# template_attiny_44.net
KiCad netlist of a schematic drawn in EAGLE
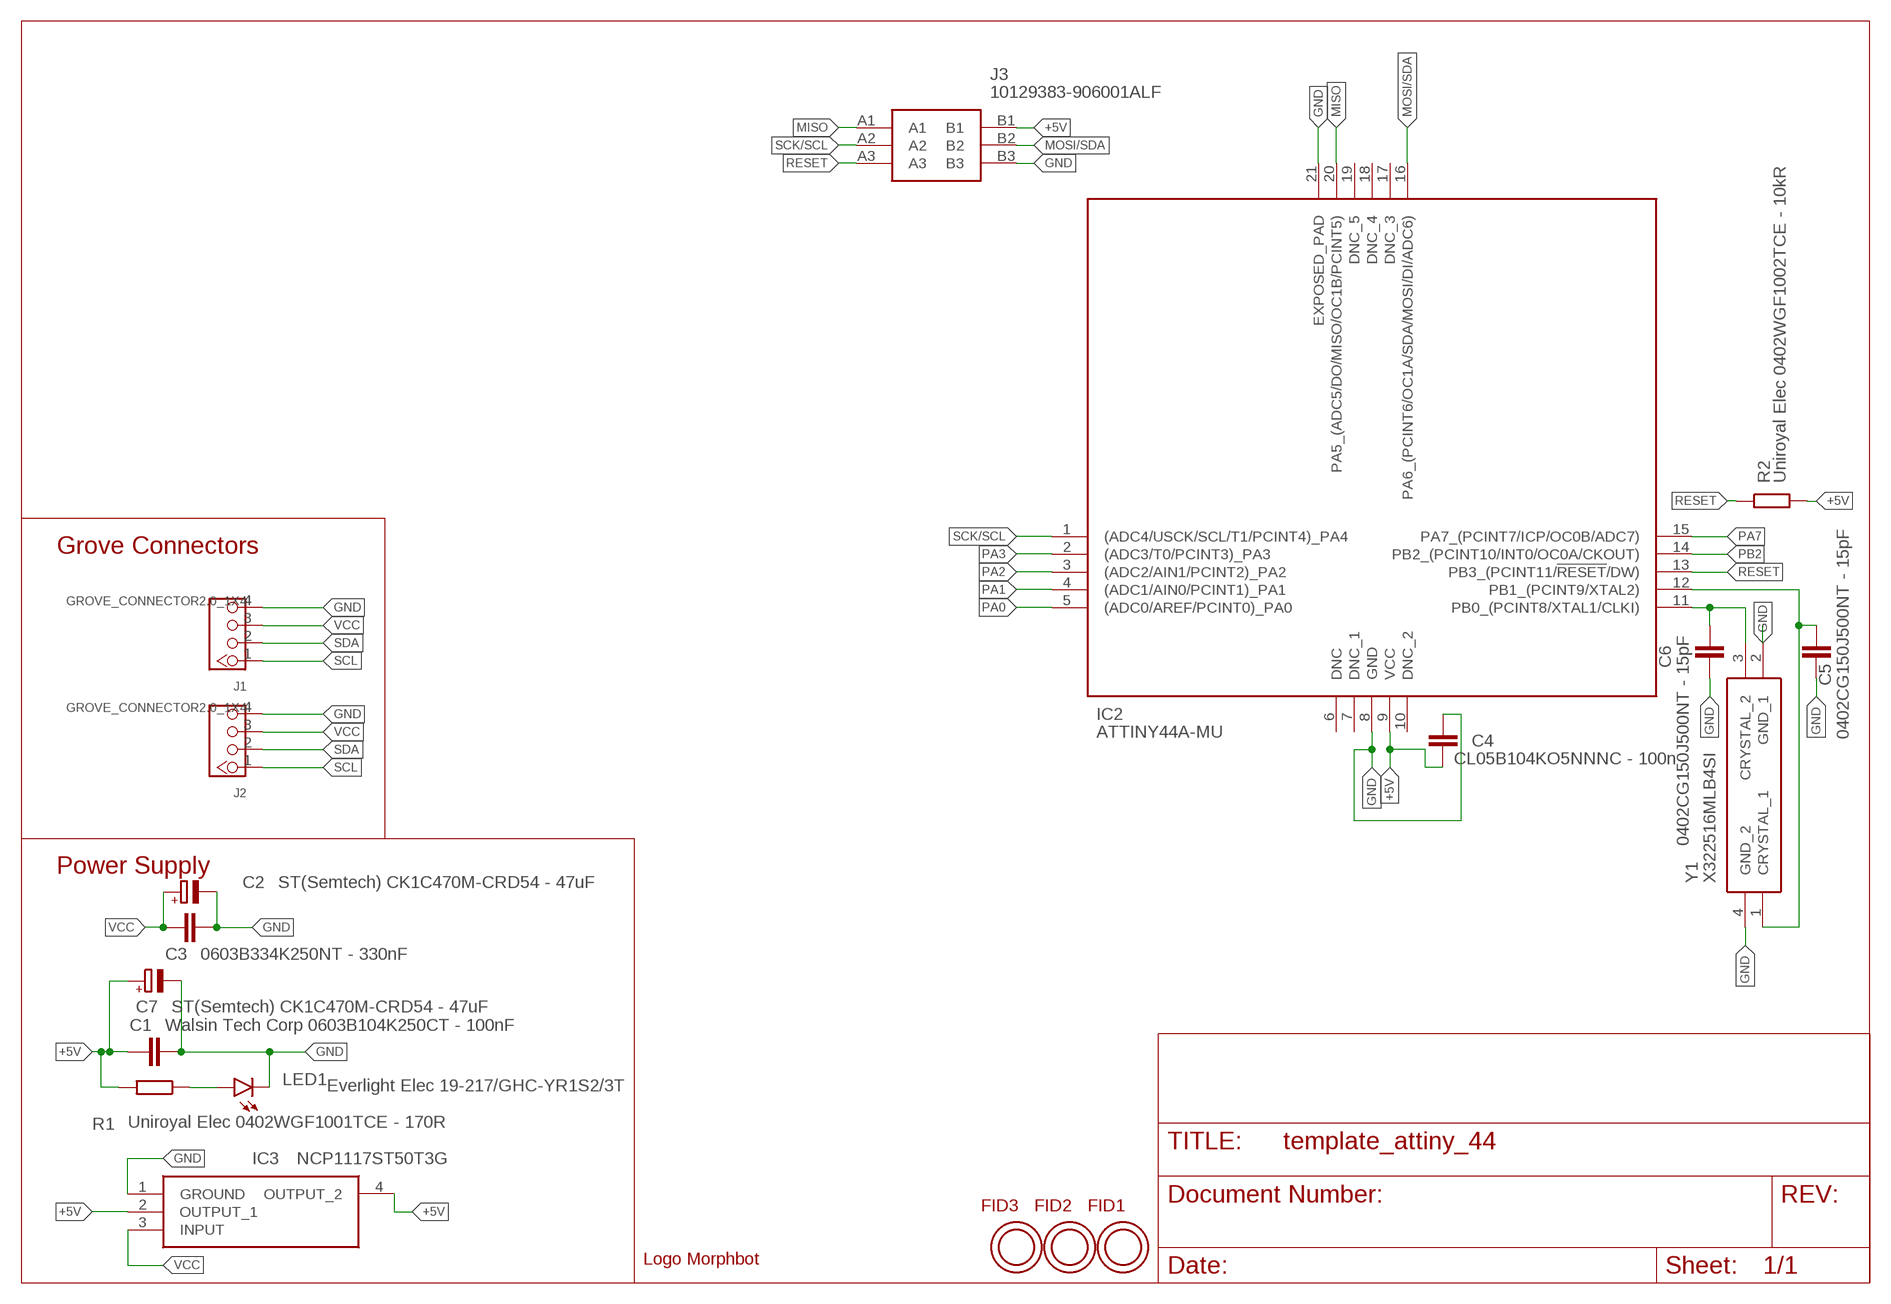
[diagram p0: schematic, sheet 1]

(export (version "E")
  (design (tool "Eeschema 10.0.6"))
  (components
    (comp (ref "C1")
      (value "Walsin Tech Corp 0603B104K250CT - 100nF")
      (footprint "eagle-import:C0603")
      (libsource (lib "eagle-import") (part "C-EUC0603"))
    )
    (comp (ref "C2")
      (value "ST(Semtech) CK1C470M-CRD54 - 47uF")
      (footprint "eagle-import:PANASONIC_C")
      (libsource (lib "eagle-import") (part "CPOL-EUC"))
    )
    (comp (ref "C3")
      (value "0603B334K250NT - 330nF")
      (footprint "eagle-import:C0603")
      (libsource (lib "eagle-import") (part "C-EUC0603"))
    )
    (comp (ref "C4")
      (value "CL05B104KO5NNNC - 100n")
      (footprint "eagle-import:C0402")
      (libsource (lib "eagle-import") (part "C-EUC0402"))
    )
    (comp (ref "C5")
      (value "0402CG150J500NT - 15pF")
      (footprint "eagle-import:C0402")
      (libsource (lib "eagle-import") (part "C-EUC0402"))
    )
    (comp (ref "C6")
      (value "0402CG150J500NT - 15pF")
      (footprint "eagle-import:C0402")
      (libsource (lib "eagle-import") (part "C-EUC0402"))
    )
    (comp (ref "C7")
      (value "ST(Semtech) CK1C470M-CRD54 - 47uF")
      (footprint "eagle-import:PANASONIC_C")
      (libsource (lib "eagle-import") (part "CPOL-EUC"))
    )
    (comp (ref "FID1")
      (value "OPEN-PNP-FIDUCIAL")
      (footprint "eagle-import:OPEN-PNP-FIDUCIAL")
      (libsource (lib "eagle-import") (part "OPEN-PNP-FIDUCIAL"))
    )
    (comp (ref "FID2")
      (value "OPEN-PNP-FIDUCIAL")
      (footprint "eagle-import:OPEN-PNP-FIDUCIAL")
      (libsource (lib "eagle-import") (part "OPEN-PNP-FIDUCIAL"))
    )
    (comp (ref "FID3")
      (value "OPEN-PNP-FIDUCIAL")
      (footprint "eagle-import:OPEN-PNP-FIDUCIAL")
      (libsource (lib "eagle-import") (part "OPEN-PNP-FIDUCIAL"))
    )
    (comp (ref "IC2")
      (value "ATTINY44A-MU")
      (footprint "eagle-import:QFN50P400X400X80-21N")
      (fields (field (name "MOUSER_PART_NUMBER") "556-ATTINY44A-MU"))
      (libsource (lib "eagle-import") (part "ATTINY44A-MU"))
    )
    (comp (ref "IC3")
      (value "NCP1117ST50T3G")
      (footprint "eagle-import:SOT230P700X180-4N")
      (fields (field (name "MOUSER_PART_NUMBER") "863-NCP1117ST50T3G"))
      (libsource (lib "eagle-import") (part "NCP1117ST50T3G"))
    )
    (comp (ref "J1")
      (value "GROVE_CONNECTOR2.0_1X4")
      (footprint "eagle-import:2.0_1X4_STRAIGHT")
      (libsource (lib "eagle-import") (part "GROVE_CONNECTOR2.0_1X4"))
    )
    (comp (ref "J2")
      (value "GROVE_CONNECTOR2.0_1X4")
      (footprint "eagle-import:2.0_1X4_STRAIGHT")
      (libsource (lib "eagle-import") (part "GROVE_CONNECTOR2.0_1X4"))
    )
    (comp (ref "J3")
      (value "10129383-906001ALF")
      (footprint "eagle-import:10129383906001ALF")
      (fields (field (name "MOUSER_PART_NUMBER") "649-1012938390601ALF"))
      (libsource (lib "eagle-import") (part "10129383-906001ALF"))
    )
    (comp (ref "LED1")
      (value "Everlight Elec 19-217/GHC-YR1S2/3T")
      (footprint "eagle-import:CHIPLED_0603")
      (libsource (lib "eagle-import") (part "LEDCHIPLED_0603"))
    )
    (comp (ref "R1")
      (value "Uniroyal Elec 0402WGF1001TCE - 170R")
      (footprint "eagle-import:R0402")
      (libsource (lib "eagle-import") (part "R-EU_R0402"))
    )
    (comp (ref "R2")
      (value "Uniroyal Elec 0402WGF1002TCE - 10kR")
      (footprint "eagle-import:R0402")
      (libsource (lib "eagle-import") (part "R-EU_R0402"))
    )
    (comp (ref "U$1")
      (value "LOGO_MORPHBOT5MM")
      (footprint "eagle-import:LOGO_MORPHBOT")
      (libsource (lib "eagle-import") (part "LOGO_MORPHBOT5MM"))
    )
    (comp (ref "Y1")
      (value "X322516MLB4SI")
      (footprint "eagle-import:X322516MLB4SI")
      (libsource (lib "eagle-import") (part "X322516MLB4SI"))
    )
  )
  (nets
    (net (code "1") (name "+5V") (class "Default")
      (node (ref "C1") (pin "1") (pinfunction "1_1") (pintype "passive"))
      (node (ref "C4") (pin "1") (pinfunction "1_1") (pintype "passive"))
      (node (ref "C7") (pin "+") (pinfunction "+_+") (pintype "passive"))
      (node (ref "IC2") (pin "9") (pinfunction "VCC_9") (pintype "power_in"))
      (node (ref "IC3") (pin "2") (pinfunction "OUTPUT_1_2") (pintype "bidirectional"))
      (node (ref "IC3") (pin "4") (pinfunction "OUTPUT_2_4") (pintype "bidirectional"))
      (node (ref "J3") (pin "B1") (pinfunction "B1_B1") (pintype "bidirectional"))
      (node (ref "R1") (pin "2") (pinfunction "2_2") (pintype "passive"))
      (node (ref "R2") (pin "2") (pinfunction "2_2") (pintype "passive"))
    )
    (net (code "2") (name "GND") (class "Default")
      (node (ref "C1") (pin "2") (pinfunction "2_2") (pintype "passive"))
      (node (ref "C2") (pin "-") (pinfunction "-_-") (pintype "passive"))
      (node (ref "C3") (pin "1") (pinfunction "1_1") (pintype "passive"))
      (node (ref "C4") (pin "2") (pinfunction "2_2") (pintype "passive"))
      (node (ref "C5") (pin "1") (pinfunction "1_1") (pintype "passive"))
      (node (ref "C6") (pin "1") (pinfunction "1_1") (pintype "passive"))
      (node (ref "C7") (pin "-") (pinfunction "-_-") (pintype "passive"))
      (node (ref "IC2") (pin "21") (pinfunction "EXPOSED_PAD_21") (pintype "bidirectional"))
      (node (ref "IC2") (pin "8") (pinfunction "GND_8") (pintype "power_in"))
      (node (ref "IC3") (pin "1") (pinfunction "GROUND_1") (pintype "bidirectional"))
      (node (ref "J1") (pin "4") (pinfunction "4_4") (pintype "bidirectional"))
      (node (ref "J2") (pin "4") (pinfunction "4_4") (pintype "bidirectional"))
      (node (ref "J3") (pin "B3") (pinfunction "B3_B3") (pintype "bidirectional"))
      (node (ref "LED1") (pin "C") (pinfunction "C_C") (pintype "passive"))
      (node (ref "Y1") (pin "2") (pinfunction "GND_1_2") (pintype "bidirectional"))
      (node (ref "Y1") (pin "4") (pinfunction "GND_2_4") (pintype "bidirectional"))
    )
    (net (code "3") (name "MISO") (class "Default")
      (node (ref "IC2") (pin "20") (pinfunction "PA5_(ADC5/DO/MISO/OC1B/PCINT5)_20") (pintype "input"))
      (node (ref "J3") (pin "A1") (pinfunction "A1_A1") (pintype "bidirectional"))
    )
    (net (code "4") (name "MOSI{slash}SDA") (class "Default")
      (node (ref "IC2") (pin "16") (pinfunction "PA6_(PCINT6/OC1A/SDA/MOSI/DI/ADC6)_16") (pintype "input"))
      (node (ref "J3") (pin "B2") (pinfunction "B2_B2") (pintype "bidirectional"))
    )
    (net (code "5") (name "Net-(IC2-PB0_(PCINT8{slash}XTAL1{slash}CLKI))") (class "Default")
      (node (ref "C6") (pin "2") (pinfunction "2_2") (pintype "passive"))
      (node (ref "IC2") (pin "11") (pinfunction "PB0_(PCINT8/XTAL1/CLKI)_11") (pintype "input"))
      (node (ref "Y1") (pin "3") (pinfunction "CRYSTAL_2_3") (pintype "bidirectional"))
    )
    (net (code "6") (name "Net-(IC2-PB1_(PCINT9{slash}XTAL2))") (class "Default")
      (node (ref "C5") (pin "2") (pinfunction "2_2") (pintype "passive"))
      (node (ref "IC2") (pin "12") (pinfunction "PB1_(PCINT9/XTAL2)_12") (pintype "input"))
      (node (ref "Y1") (pin "1") (pinfunction "CRYSTAL_1_1") (pintype "bidirectional"))
    )
    (net (code "7") (name "Net-(LED1-PadA)") (class "Default")
      (node (ref "LED1") (pin "A") (pinfunction "A_A") (pintype "passive"))
      (node (ref "R1") (pin "1") (pinfunction "1_1") (pintype "passive"))
    )
    (net (code "8") (name "PA0") (class "Default")
      (node (ref "IC2") (pin "5") (pinfunction "(ADC0/AREF/PCINT0)_PA0_5") (pintype "input"))
    )
    (net (code "9") (name "PA1") (class "Default")
      (node (ref "IC2") (pin "4") (pinfunction "(ADC1/AIN0/PCINT1)_PA1_4") (pintype "input"))
    )
    (net (code "10") (name "PA2") (class "Default")
      (node (ref "IC2") (pin "3") (pinfunction "(ADC2/AIN1/PCINT2)_PA2_3") (pintype "input"))
    )
    (net (code "11") (name "PA3") (class "Default")
      (node (ref "IC2") (pin "2") (pinfunction "(ADC3/T0/PCINT3)_PA3_2") (pintype "input"))
    )
    (net (code "12") (name "PA7") (class "Default")
      (node (ref "IC2") (pin "15") (pinfunction "PA7_(PCINT7/ICP/OC0B/ADC7)_15") (pintype "input"))
    )
    (net (code "13") (name "PB2") (class "Default")
      (node (ref "IC2") (pin "14") (pinfunction "PB2_(PCINT10/INT0/OC0A/CKOUT)_14") (pintype "output"))
    )
    (net (code "14") (name "RESET") (class "Default")
      (node (ref "IC2") (pin "13") (pinfunction "PB3_(PCINT11/~{RESET}/DW)_13") (pintype "input"))
      (node (ref "J3") (pin "A3") (pinfunction "A3_A3") (pintype "bidirectional"))
      (node (ref "R2") (pin "1") (pinfunction "1_1") (pintype "passive"))
    )
    (net (code "15") (name "SCK{slash}SCL") (class "Default")
      (node (ref "IC2") (pin "1") (pinfunction "(ADC4/USCK/SCL/T1/PCINT4)_PA4_1") (pintype "input"))
      (node (ref "J3") (pin "A2") (pinfunction "A2_A2") (pintype "bidirectional"))
    )
    (net (code "16") (name "SCL") (class "Default")
      (node (ref "J1") (pin "1") (pinfunction "1_1") (pintype "bidirectional"))
      (node (ref "J2") (pin "1") (pinfunction "1_1") (pintype "bidirectional"))
    )
    (net (code "17") (name "SDA") (class "Default")
      (node (ref "J1") (pin "2") (pinfunction "2_2") (pintype "bidirectional"))
      (node (ref "J2") (pin "2") (pinfunction "2_2") (pintype "bidirectional"))
    )
    (net (code "18") (name "VCC") (class "Default")
      (node (ref "C2") (pin "+") (pinfunction "+_+") (pintype "passive"))
      (node (ref "C3") (pin "2") (pinfunction "2_2") (pintype "passive"))
      (node (ref "IC3") (pin "3") (pinfunction "INPUT_3") (pintype "bidirectional"))
      (node (ref "J1") (pin "3") (pinfunction "3_3") (pintype "bidirectional"))
      (node (ref "J2") (pin "3") (pinfunction "3_3") (pintype "bidirectional"))
    )
    (net (code "19") (name "unconnected-(IC2-DNC-Pad6)") (class "Default")
      (node (ref "IC2") (pin "6") (pinfunction "DNC_6") (pintype "bidirectional"))
    )
    (net (code "20") (name "unconnected-(IC2-DNC_1-Pad7)") (class "Default")
      (node (ref "IC2") (pin "7") (pinfunction "DNC_1_7") (pintype "bidirectional"))
    )
    (net (code "21") (name "unconnected-(IC2-DNC_2-Pad10)") (class "Default")
      (node (ref "IC2") (pin "10") (pinfunction "DNC_2_10") (pintype "bidirectional"))
    )
    (net (code "22") (name "unconnected-(IC2-DNC_3-Pad17)") (class "Default")
      (node (ref "IC2") (pin "17") (pinfunction "DNC_3_17") (pintype "bidirectional"))
    )
    (net (code "23") (name "unconnected-(IC2-DNC_4-Pad18)") (class "Default")
      (node (ref "IC2") (pin "18") (pinfunction "DNC_4_18") (pintype "bidirectional"))
    )
    (net (code "24") (name "unconnected-(IC2-DNC_5-Pad19)") (class "Default")
      (node (ref "IC2") (pin "19") (pinfunction "DNC_5_19") (pintype "bidirectional"))
    )
  )
)
